# AP33771.net
KiCad netlist of a schematic drawn in Altium Designer
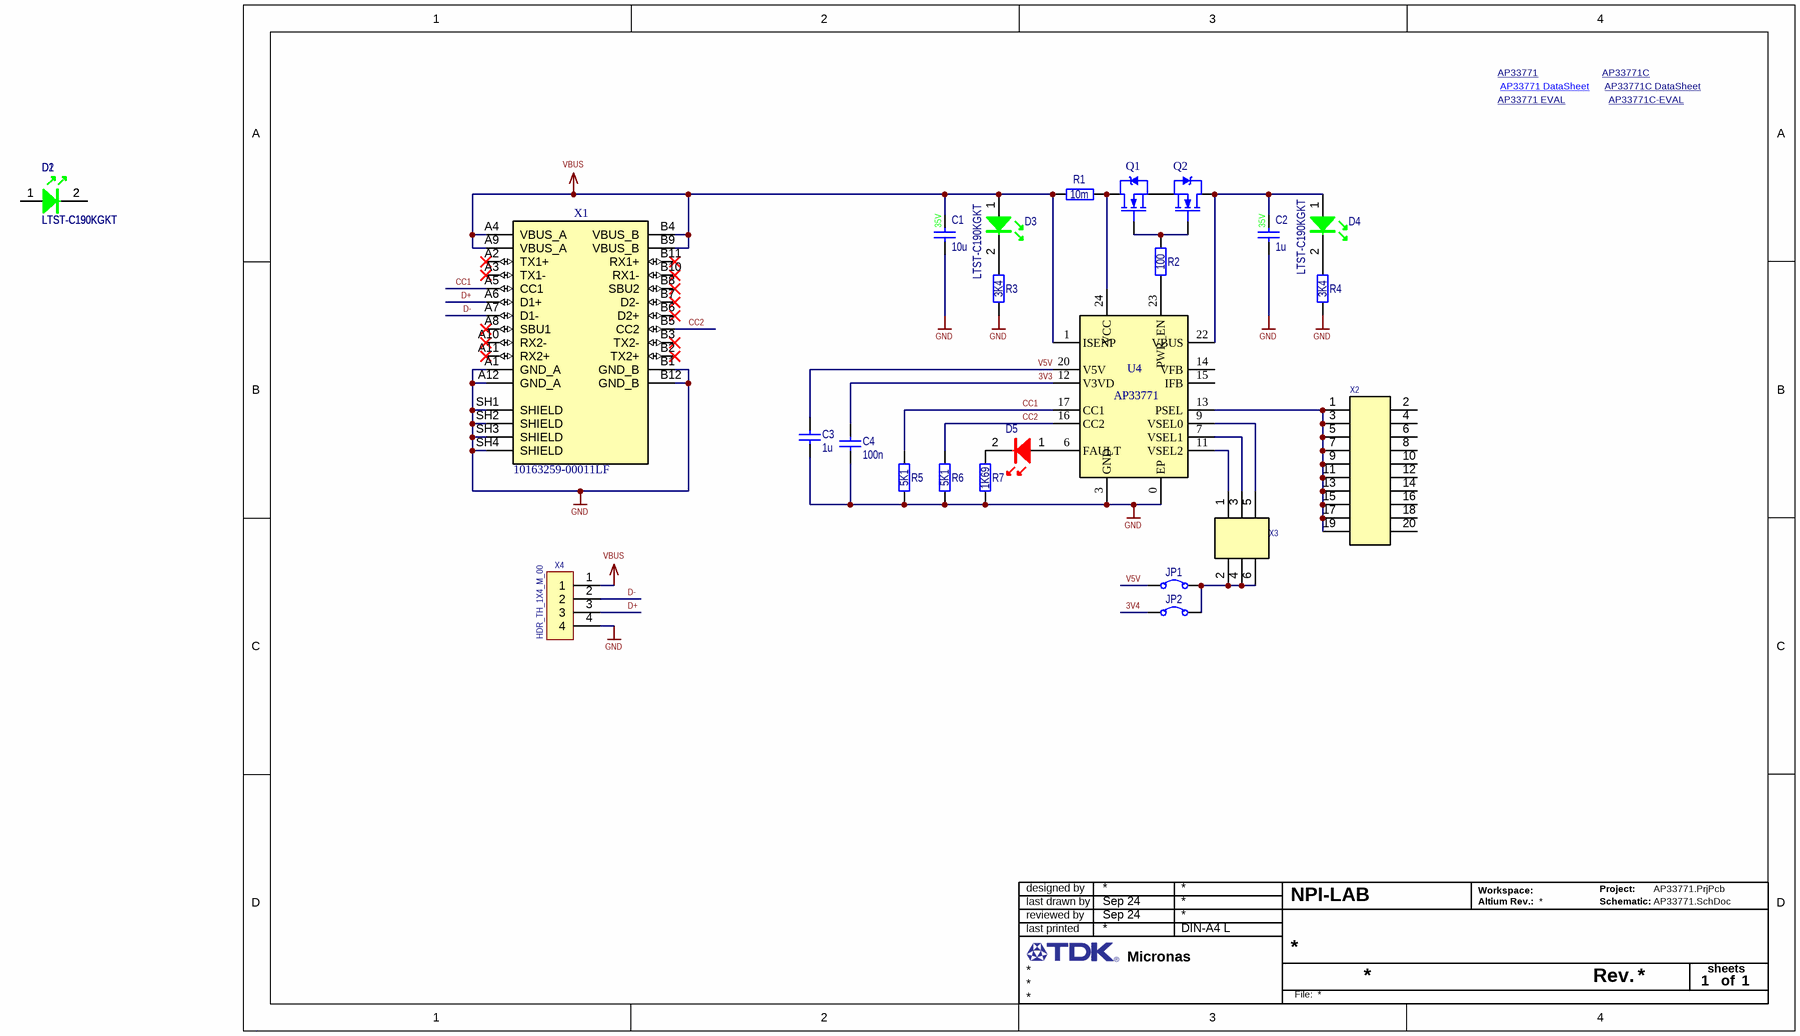
[diagram p0: AP33771.SchDoc]

(export (version "E")
  (design (tool "Eeschema 10.0.6"))
  (components
    (comp (ref "C1")
      (value "35V")
      (footprint "CAPC0603")
      (description "Capacitor; X5R; 10u; 0603; 35V; 20%; -55°C ~ 85°C")
      (fields
        (field (name "MANUFACTURER") "Murata Electronics")
        (field (name "MANUFACTURER PART NUMBER") "GRM188R6YA106MA73D")
        (field (name "ALTIUM_VALUE") "10u")
      )
      (libsource (lib "symbols") (part "10u_0603_35V_X5R_20%"))
    )
    (comp (ref "C2")
      (value "35V")
      (footprint "CAPC0603")
      (description "Capacitor; X7R; 1u; 0603; 35V; 10%; -55°C ~ 125°C")
      (fields
        (field (name "MANUFACTURER") "Taiyo Yuden")
        (field (name "MANUFACTURER PART NUMBER") "GMK107AB7105KAHT")
        (field (name "ALTIUM_VALUE") "1u")
      )
      (libsource (lib "symbols") (part "1u_0603_35V_X7R_10%"))
    )
    (comp (ref "C3")
      (value "1u")
      (footprint "CAPC0402")
      (description "Capacitor; Ceramic; 1u; 0402; 10V; X5R; 10%; -55°C ~ 85°C")
      (fields
        (field (name "MANUFACTURER") "Samsung Electro-Mechanics")
        (field (name "MANUFACTURER PART NUMBER") "CL05A105KP5NNNC")
      )
      (libsource (lib "Capacitors") (part "1u_0402_10V_X5R_10%"))
    )
    (comp (ref "C4")
      (value "100n")
      (footprint "CAPC0402")
      (description "Capacitor; Ceramic; 100n; 0402; 10V; X7R; 5%; -55°C ~ 125°C")
      (fields
        (field (name "MANUFACTURER") "KEMET")
        (field (name "MANUFACTURER PART NUMBER") "C0402C104J8RACTU")
      )
      (libsource (lib "Capacitors") (part "100n_0402_10V_X7R_5%"))
    )
    (comp (ref "D1")
      (value "LTST-C190KGKT")
      (footprint "LED0603G")
      (description "LED; Green; 571nm; SMD; 0603")
      (fields (field (name "MANUFACTURER") "Lite-On Inc."))
      (libsource (lib "symbols") (part "LED_GN_LTST-C190KGKT"))
    )
    (comp (ref "D2")
      (value "LTST-C190KGKT")
      (footprint "LED0603G")
      (description "LED; Green; 571nm; SMD; 0603")
      (fields (field (name "MANUFACTURER") "Lite-On Inc."))
      (libsource (lib "symbols") (part "LED_GN_LTST-C190KGKT"))
    )
    (comp (ref "D3")
      (value "LTST-C190KGKT")
      (footprint "LED0603G")
      (description "LED; Green; 571nm; SMD; 0603")
      (fields (field (name "MANUFACTURER") "Lite-On Inc."))
      (libsource (lib "symbols") (part "LED_GN_LTST-C190KGKT"))
    )
    (comp (ref "D4")
      (value "LTST-C190KGKT")
      (footprint "LED0603G")
      (description "LED; Green; 571nm; SMD; 0603")
      (fields (field (name "MANUFACTURER") "Lite-On Inc."))
      (libsource (lib "symbols") (part "LED_GN_LTST-C190KGKT"))
    )
    (comp (ref "D5")
      (value "LTST-C190KGKT")
      (footprint "LED0603R")
      (description "LED; RED; 571nm; SMD; 0603")
      (fields
        (field (name "MANUFACTURER") "Lite-On Inc.")
        (field (name "MANUFACTURER PART NUMBER") "LTST-C190KRKT")
      )
      (libsource (lib "symbols") (part "LED_GN_LTST-C190KRKT"))
    )
    (comp (ref "JP1")
      (value "5110 Keystone")
      (footprint "JumperSMD_0603")
      (description "Jumper; Chip; 0R; 0603; 500mW")
      (fields (field (name "MANUFACTURER") "Keystone") (field (name "MANUFACTURER PART NUMBER") "5110"))
      (libsource (lib "Jumpers") (part "JMP_0R_0603"))
    )
    (comp (ref "JP2")
      (value "5110 Keystone")
      (footprint "JumperSMD_0603")
      (description "Jumper; Chip; 0R; 0603; 500mW")
      (fields (field (name "MANUFACTURER") "Keystone") (field (name "MANUFACTURER PART NUMBER") "5110"))
      (libsource (lib "Jumpers") (part "JMP_0R_0603"))
    )
    (comp (ref "Q1")
      (value "DMN3008SFG")
      (footprint "PowerDI3333-8")
      (description "MOSFET N-CH 30V 16A PWRDI3333")
      (fields
        (field (name "MANUFACTURER") "Diodes Incorporated")
        (field (name "MANUFACTURER PART NUMBER") "DMN3008SFG-7")
      )
      (libsource (lib "symbols") (part "DMN3008SFG"))
    )
    (comp (ref "Q2")
      (value "DMN3008SFG")
      (footprint "PowerDI3333-8")
      (description "MOSFET N-CH 30V 16A PWRDI3333")
      (fields
        (field (name "MANUFACTURER") "Diodes Incorporated")
        (field (name "MANUFACTURER PART NUMBER") "DMN3008SFG-7")
      )
      (libsource (lib "symbols") (part "DMN3008SFG"))
    )
    (comp (ref "R1")
      (value "10m")
      (footprint "RESC1206")
      (description "Resistor; Chip; 10mR; 1206; 1%; 100ppm; 1W; -55°C ~ 170°C")
      (fields
        (field (name "MANUFACTURER") "YAGEO")
        (field (name "MANUFACTURER PART NUMBER") "PE1206FRF470R01L")
      )
      (libsource (lib "symbols") (part "10m_1206_63mW_1%_100ppm_1"))
    )
    (comp (ref "R2")
      (value "100")
      (footprint "RESC0402")
      (description "Resistor; Chip; 100R; 0402; 1%; 100ppm; 63mW; -55°C ~ 155°C")
      (fields (field (name "Comment") "100R_0402_63mW_1%_100ppm_1"))
      (libsource (lib "symbols") (part "100R_0402_63mW_1%_100ppm_1"))
    )
    (comp (ref "R3")
      (value "3K4")
      (footprint "RESC0402")
      (description "Resistor; Chip; 3K4; 0402; 1%; 100ppm; 63mW; -55°C ~ 155°C")
      (fields
        (field (name "MANUFACTURER") "YAGEO")
        (field (name "MANUFACTURER PART NUMBER") "AC0402FR-073K4L")
      )
      (libsource (lib "symbols") (part "3K4_0402_63mW_1%_100ppm"))
    )
    (comp (ref "R4")
      (value "3K4")
      (footprint "RESC0402")
      (description "Resistor; Chip; 3K4; 0402; 1%; 100ppm; 63mW; -55°C ~ 155°C")
      (fields
        (field (name "MANUFACTURER") "YAGEO")
        (field (name "MANUFACTURER PART NUMBER") "AC0402FR-073K4L")
      )
      (libsource (lib "symbols") (part "3K4_0402_63mW_1%_100ppm"))
    )
    (comp (ref "R5")
      (value "5K1")
      (footprint "RESC0402")
      (description "Resistor; Chip;  5K1; 0402; 1%; 100ppm; 63mW; -55°C ~ 155°C")
      (fields (field (name "Comment") "5K1_0402_63mW_1%_100ppm"))
      (libsource (lib "symbols") (part "5K1_0402_63mW_1%_100ppm"))
    )
    (comp (ref "R6")
      (value "5K1")
      (footprint "RESC0402")
      (description "Resistor; Chip;  5K1; 0402; 1%; 100ppm; 63mW; -55°C ~ 155°C")
      (fields (field (name "Comment") "5K1_0402_63mW_1%_100ppm"))
      (libsource (lib "symbols") (part "5K1_0402_63mW_1%_100ppm"))
    )
    (comp (ref "R7")
      (value "1K69")
      (footprint "RESC0402")
      (description "Resistor; Chip; 1K69; 0402; 1%; 100ppm; 63mW; -55°C ~ 155°C")
      (fields (field (name "Comment") "1K69_0402_63mW_1%_100ppm"))
      (libsource (lib "symbols") (part "1K69_0402_63mW_1%_100ppm"))
    )
    (comp (ref "U4")
      (value "AP33771")
      (footprint "W-QFN4040-24")
      (description "USB PD SINK CONTROLLER")
      (fields
        (field (name "MANUFACTURER") "Diodes Incorporated")
        (field (name "MANUFACTURER PART NUMBER") "AP33771DKZ-13")
      )
      (libsource (lib "symbols") (part "AP33771"))
    )
    (comp (ref "X1")
      (value "10163259-00011LF")
      (footprint "10163259-00011LF")
      (description "USB 3.2 TYPE C GEN 2 RECEPTACLE")
      (fields (field (name "MANUFACTURER") "Amphenol ICC (FCI)") (field (name "Comment") "USBC"))
      (libsource (lib "symbols") (part "10163259-00011LF"))
    )
    (comp (ref "X2")
      (value "HMTSW-110-07-G-D-240")
      (footprint "HDR_TH_2X10_M_00")
      (description "Header; 2x10 pins; Male; Straight; Pitch 2.54mm; Samtec HMTSW Series")
      (fields
        (field (name "MANUFACTURER") "Samtec Inc.")
        (field (name "MANUFACTURER PART NUMBER") "HMTSW-148-07-G-S-240")
      )
      (libsource (lib "symbols") (part "HDR_TH_2X10_M_00"))
    )
    (comp (ref "X3")
      (value "HMTSW-103-07-G-D-240")
      (footprint "HDR_TH_2X3_M_00")
      (description "Header; 2x3 pins; Male; Straight; Pitch 2.54mm; Samtec HMTSW Series")
      (fields
        (field (name "MANUFACTURER") "Samtec Inc.")
        (field (name "MANUFACTURER PART NUMBER") "HMTSW-148-07-G-S-240")
      )
      (libsource (lib "symbols") (part "HDR_TH_2X3_M_00_1"))
    )
    (comp (ref "X4")
      (value "HDR_TH_1X4_M_00")
      (footprint "HDR_TH_1X4_M_00")
      (description "Header; 1x4 pins; Male; Straight; Pitch 2.54mm; Samtec HMTSW Series")
      (fields
        (field (name "MANUFACTURER") "Samtec Inc.")
        (field (name "MANUFACTURER PART NUMBER") "HMTSW-104-07-G-S-240")
      )
      (libsource (lib "symbols") (part "HDR_TH_1X4_M_00"))
    )
  )
  (nets
    (net (code "1") (name "/3V3") (class "Default")
      (node (ref "C4") (pin "2") (pinfunction "2_2") (pintype "passive"))
      (node (ref "U4") (pin "12") (pinfunction "V3VD_12") (pintype "passive"))
    )
    (net (code "2") (name "/3V4") (class "Default")
      (node (ref "JP2") (pin "1") (pinfunction "1_1") (pintype "passive"))
    )
    (net (code "3") (name "/CC1") (class "Default")
      (node (ref "R5") (pin "2") (pinfunction "2_2") (pintype "passive"))
      (node (ref "U4") (pin "17") (pinfunction "CC1_17") (pintype "passive"))
      (node (ref "X1") (pin "A5") (pinfunction "CC1_A5") (pintype "bidirectional"))
    )
    (net (code "4") (name "/CC2") (class "Default")
      (node (ref "R6") (pin "2") (pinfunction "2_2") (pintype "passive"))
      (node (ref "U4") (pin "16") (pinfunction "CC2_16") (pintype "passive"))
      (node (ref "X1") (pin "B5") (pinfunction "CC2_B5") (pintype "bidirectional"))
    )
    (net (code "5") (name "/D+") (class "Default")
      (node (ref "X1") (pin "A6") (pinfunction "D1+_A6") (pintype "bidirectional"))
      (node (ref "X4") (pin "3") (pinfunction "3_3") (pintype "passive"))
    )
    (net (code "6") (name "/D-") (class "Default")
      (node (ref "X1") (pin "A7") (pinfunction "D1-_A7") (pintype "bidirectional"))
      (node (ref "X4") (pin "2") (pinfunction "2_2") (pintype "passive"))
    )
    (net (code "7") (name "/V5V") (class "Default")
      (node (ref "C3") (pin "2") (pinfunction "2_2") (pintype "passive"))
      (node (ref "JP1") (pin "1") (pinfunction "1_1") (pintype "passive"))
      (node (ref "U4") (pin "20") (pinfunction "V5V_20") (pintype "passive"))
    )
    (net (code "8") (name "GND") (class "Default")
      (node (ref "C1") (pin "1") (pinfunction "1_1") (pintype "passive"))
      (node (ref "C2") (pin "1") (pinfunction "1_1") (pintype "passive"))
      (node (ref "C3") (pin "1") (pinfunction "1_1") (pintype "passive"))
      (node (ref "C4") (pin "1") (pinfunction "1_1") (pintype "passive"))
      (node (ref "R3") (pin "1") (pinfunction "1_1") (pintype "passive"))
      (node (ref "R4") (pin "1") (pinfunction "1_1") (pintype "passive"))
      (node (ref "R5") (pin "1") (pinfunction "1_1") (pintype "passive"))
      (node (ref "R6") (pin "1") (pinfunction "1_1") (pintype "passive"))
      (node (ref "R7") (pin "1") (pinfunction "1_1") (pintype "passive"))
      (node (ref "U4") (pin "0") (pinfunction "EP_0") (pintype "passive"))
      (node (ref "U4") (pin "3") (pinfunction "GND_3") (pintype "passive"))
      (node (ref "X1") (pin "A1") (pinfunction "GND_A_A1") (pintype "power_in"))
      (node (ref "X1") (pin "A12") (pinfunction "GND_A_A12") (pintype "power_in"))
      (node (ref "X1") (pin "B1") (pinfunction "GND_B_B1") (pintype "power_in"))
      (node (ref "X1") (pin "B12") (pinfunction "GND_B_B12") (pintype "power_in"))
      (node (ref "X1") (pin "SH1") (pinfunction "SHIELD_SH1") (pintype "passive"))
      (node (ref "X1") (pin "SH2") (pinfunction "SHIELD_SH2") (pintype "passive"))
      (node (ref "X1") (pin "SH3") (pinfunction "SHIELD_SH3") (pintype "passive"))
      (node (ref "X1") (pin "SH4") (pinfunction "SHIELD_SH4") (pintype "passive"))
      (node (ref "X4") (pin "4") (pinfunction "4_4") (pintype "passive"))
    )
    (net (code "9") (name "Net-(D1-A)") (class "Default")
      (node (ref "D1") (pin "1") (pinfunction "A_1") (pintype "passive"))
      (node (ref "D2") (pin "1") (pinfunction "A_1") (pintype "passive"))
    )
    (net (code "10") (name "Net-(D1-K)") (class "Default")
      (node (ref "D1") (pin "2") (pinfunction "K_2") (pintype "passive"))
      (node (ref "D2") (pin "2") (pinfunction "K_2") (pintype "passive"))
    )
    (net (code "11") (name "Net-(D3-K)") (class "Default")
      (node (ref "D3") (pin "2") (pinfunction "K_2") (pintype "passive"))
      (node (ref "R3") (pin "2") (pinfunction "2_2") (pintype "passive"))
    )
    (net (code "12") (name "Net-(D4-A)") (class "Default")
      (node (ref "C2") (pin "2") (pinfunction "2_2") (pintype "passive"))
      (node (ref "D4") (pin "1") (pinfunction "A_1") (pintype "passive"))
      (node (ref "Q2") (pin "3") (pinfunction "D_3") (pintype "passive"))
      (node (ref "U4") (pin "22") (pinfunction "VBUS_22") (pintype "passive"))
    )
    (net (code "13") (name "Net-(D4-K)") (class "Default")
      (node (ref "D4") (pin "2") (pinfunction "K_2") (pintype "passive"))
      (node (ref "R4") (pin "2") (pinfunction "2_2") (pintype "passive"))
    )
    (net (code "14") (name "Net-(D5-A)") (class "Default")
      (node (ref "D5") (pin "1") (pinfunction "A_1") (pintype "passive"))
      (node (ref "U4") (pin "6") (pinfunction "FAULT_6") (pintype "passive"))
    )
    (net (code "15") (name "Net-(D5-K)") (class "Default")
      (node (ref "D5") (pin "2") (pinfunction "K_2") (pintype "passive"))
      (node (ref "R7") (pin "2") (pinfunction "2_2") (pintype "passive"))
    )
    (net (code "16") (name "Net-(JP1-Pad2)") (class "Default")
      (node (ref "JP1") (pin "2") (pinfunction "2_2") (pintype "passive"))
      (node (ref "JP2") (pin "2") (pinfunction "2_2") (pintype "passive"))
      (node (ref "X3") (pin "2") (pinfunction "2_2") (pintype "passive"))
      (node (ref "X3") (pin "4") (pinfunction "4_4") (pintype "passive"))
      (node (ref "X3") (pin "6") (pinfunction "6_6") (pintype "passive"))
    )
    (net (code "17") (name "Net-(Q1-D)") (class "Default")
      (node (ref "Q1") (pin "3") (pinfunction "D_3") (pintype "passive"))
      (node (ref "R1") (pin "2") (pinfunction "2_2") (pintype "passive"))
      (node (ref "U4") (pin "24") (pinfunction "VCC_24") (pintype "passive"))
    )
    (net (code "18") (name "Net-(Q1-G)") (class "Default")
      (node (ref "Q1") (pin "1") (pinfunction "G_1") (pintype "passive"))
      (node (ref "Q2") (pin "1") (pinfunction "G_1") (pintype "passive"))
      (node (ref "R2") (pin "2") (pinfunction "2_2") (pintype "passive"))
    )
    (net (code "19") (name "Net-(Q1-S)") (class "Default")
      (node (ref "Q1") (pin "2") (pinfunction "S_2") (pintype "passive"))
      (node (ref "Q2") (pin "2") (pinfunction "S_2") (pintype "passive"))
    )
    (net (code "20") (name "Net-(U4-PSEL)") (class "Default")
      (node (ref "U4") (pin "13") (pinfunction "PSEL_13") (pintype "passive"))
      (node (ref "X2") (pin "1") (pinfunction "1_1") (pintype "passive"))
      (node (ref "X2") (pin "11") (pinfunction "11_11") (pintype "passive"))
      (node (ref "X2") (pin "13") (pinfunction "13_13") (pintype "passive"))
      (node (ref "X2") (pin "15") (pinfunction "15_15") (pintype "passive"))
      (node (ref "X2") (pin "17") (pinfunction "17_17") (pintype "passive"))
      (node (ref "X2") (pin "19") (pinfunction "19_19") (pintype "passive"))
      (node (ref "X2") (pin "3") (pinfunction "3_3") (pintype "passive"))
      (node (ref "X2") (pin "5") (pinfunction "5_5") (pintype "passive"))
      (node (ref "X2") (pin "7") (pinfunction "7_7") (pintype "passive"))
      (node (ref "X2") (pin "9") (pinfunction "9_9") (pintype "passive"))
    )
    (net (code "21") (name "Net-(U4-PWR_EN)") (class "Default")
      (node (ref "R2") (pin "1") (pinfunction "1_1") (pintype "passive"))
      (node (ref "U4") (pin "23") (pinfunction "PWR_EN_23") (pintype "passive"))
    )
    (net (code "22") (name "Net-(U4-VSEL0)") (class "Default")
      (node (ref "U4") (pin "9") (pinfunction "VSEL0_9") (pintype "passive"))
      (node (ref "X3") (pin "5") (pinfunction "5_5") (pintype "passive"))
    )
    (net (code "23") (name "Net-(U4-VSEL1)") (class "Default")
      (node (ref "U4") (pin "7") (pinfunction "VSEL1_7") (pintype "passive"))
      (node (ref "X3") (pin "3") (pinfunction "3_3") (pintype "passive"))
    )
    (net (code "24") (name "Net-(U4-VSEL2)") (class "Default")
      (node (ref "U4") (pin "11") (pinfunction "VSEL2_11") (pintype "passive"))
      (node (ref "X3") (pin "1") (pinfunction "1_1") (pintype "passive"))
    )
    (net (code "25") (name "VBUS") (class "Default")
      (node (ref "C1") (pin "2") (pinfunction "2_2") (pintype "passive"))
      (node (ref "D3") (pin "1") (pinfunction "A_1") (pintype "passive"))
      (node (ref "R1") (pin "1") (pinfunction "1_1") (pintype "passive"))
      (node (ref "U4") (pin "1") (pinfunction "ISENP_1") (pintype "passive"))
      (node (ref "X1") (pin "A4") (pinfunction "VBUS_A_A4") (pintype "power_in"))
      (node (ref "X1") (pin "A9") (pinfunction "VBUS_A_A9") (pintype "power_in"))
      (node (ref "X1") (pin "B4") (pinfunction "VBUS_B_B4") (pintype "power_in"))
      (node (ref "X1") (pin "B9") (pinfunction "VBUS_B_B9") (pintype "power_in"))
      (node (ref "X4") (pin "1") (pinfunction "1_1") (pintype "passive"))
    )
    (net (code "26") (name "unconnected-(U4-IFB-Pad15)") (class "Default")
      (node (ref "U4") (pin "15") (pinfunction "IFB_15") (pintype "passive"))
    )
    (net (code "27") (name "unconnected-(U4-VFB-Pad14)") (class "Default")
      (node (ref "U4") (pin "14") (pinfunction "VFB_14") (pintype "passive"))
    )
    (net (code "28") (name "unconnected-(X1-D2+-PadB6)") (class "Default")
      (node (ref "X1") (pin "B6") (pinfunction "D2+_B6") (pintype "bidirectional+no_connect"))
    )
    (net (code "29") (name "unconnected-(X1-D2--PadB7)") (class "Default")
      (node (ref "X1") (pin "B7") (pinfunction "D2-_B7") (pintype "bidirectional+no_connect"))
    )
    (net (code "30") (name "unconnected-(X1-RX1+-PadB11)") (class "Default")
      (node (ref "X1") (pin "B11") (pinfunction "RX1+_B11") (pintype "bidirectional+no_connect"))
    )
    (net (code "31") (name "unconnected-(X1-RX1--PadB10)") (class "Default")
      (node (ref "X1") (pin "B10") (pinfunction "RX1-_B10") (pintype "bidirectional+no_connect"))
    )
    (net (code "32") (name "unconnected-(X1-RX2+-PadA11)") (class "Default")
      (node (ref "X1") (pin "A11") (pinfunction "RX2+_A11") (pintype "bidirectional+no_connect"))
    )
    (net (code "33") (name "unconnected-(X1-RX2--PadA10)") (class "Default")
      (node (ref "X1") (pin "A10") (pinfunction "RX2-_A10") (pintype "bidirectional+no_connect"))
    )
    (net (code "34") (name "unconnected-(X1-SBU1-PadA8)") (class "Default")
      (node (ref "X1") (pin "A8") (pinfunction "SBU1_A8") (pintype "bidirectional+no_connect"))
    )
    (net (code "35") (name "unconnected-(X1-SBU2-PadB8)") (class "Default")
      (node (ref "X1") (pin "B8") (pinfunction "SBU2_B8") (pintype "bidirectional+no_connect"))
    )
    (net (code "36") (name "unconnected-(X1-TX1+-PadA2)") (class "Default")
      (node (ref "X1") (pin "A2") (pinfunction "TX1+_A2") (pintype "bidirectional+no_connect"))
    )
    (net (code "37") (name "unconnected-(X1-TX1--PadA3)") (class "Default")
      (node (ref "X1") (pin "A3") (pinfunction "TX1-_A3") (pintype "bidirectional+no_connect"))
    )
    (net (code "38") (name "unconnected-(X1-TX2+-PadB2)") (class "Default")
      (node (ref "X1") (pin "B2") (pinfunction "TX2+_B2") (pintype "bidirectional+no_connect"))
    )
    (net (code "39") (name "unconnected-(X1-TX2--PadB3)") (class "Default")
      (node (ref "X1") (pin "B3") (pinfunction "TX2-_B3") (pintype "bidirectional+no_connect"))
    )
    (net (code "40") (name "unconnected-(X2-Pad2)") (class "Default")
      (node (ref "X2") (pin "2") (pinfunction "2_2") (pintype "passive"))
    )
    (net (code "41") (name "unconnected-(X2-Pad4)") (class "Default")
      (node (ref "X2") (pin "4") (pinfunction "4_4") (pintype "passive"))
    )
    (net (code "42") (name "unconnected-(X2-Pad6)") (class "Default")
      (node (ref "X2") (pin "6") (pinfunction "6_6") (pintype "passive"))
    )
    (net (code "43") (name "unconnected-(X2-Pad8)") (class "Default")
      (node (ref "X2") (pin "8") (pinfunction "8_8") (pintype "passive"))
    )
    (net (code "44") (name "unconnected-(X2-Pad10)") (class "Default")
      (node (ref "X2") (pin "10") (pinfunction "10_10") (pintype "passive"))
    )
    (net (code "45") (name "unconnected-(X2-Pad12)") (class "Default")
      (node (ref "X2") (pin "12") (pinfunction "12_12") (pintype "passive"))
    )
    (net (code "46") (name "unconnected-(X2-Pad14)") (class "Default")
      (node (ref "X2") (pin "14") (pinfunction "14_14") (pintype "passive"))
    )
    (net (code "47") (name "unconnected-(X2-Pad16)") (class "Default")
      (node (ref "X2") (pin "16") (pinfunction "16_16") (pintype "passive"))
    )
    (net (code "48") (name "unconnected-(X2-Pad18)") (class "Default")
      (node (ref "X2") (pin "18") (pinfunction "18_18") (pintype "passive"))
    )
    (net (code "49") (name "unconnected-(X2-Pad20)") (class "Default")
      (node (ref "X2") (pin "20") (pinfunction "20_20") (pintype "passive"))
    )
  )
)
